# Circuit.net
KiCad netlist of a schematic drawn in EAGLE
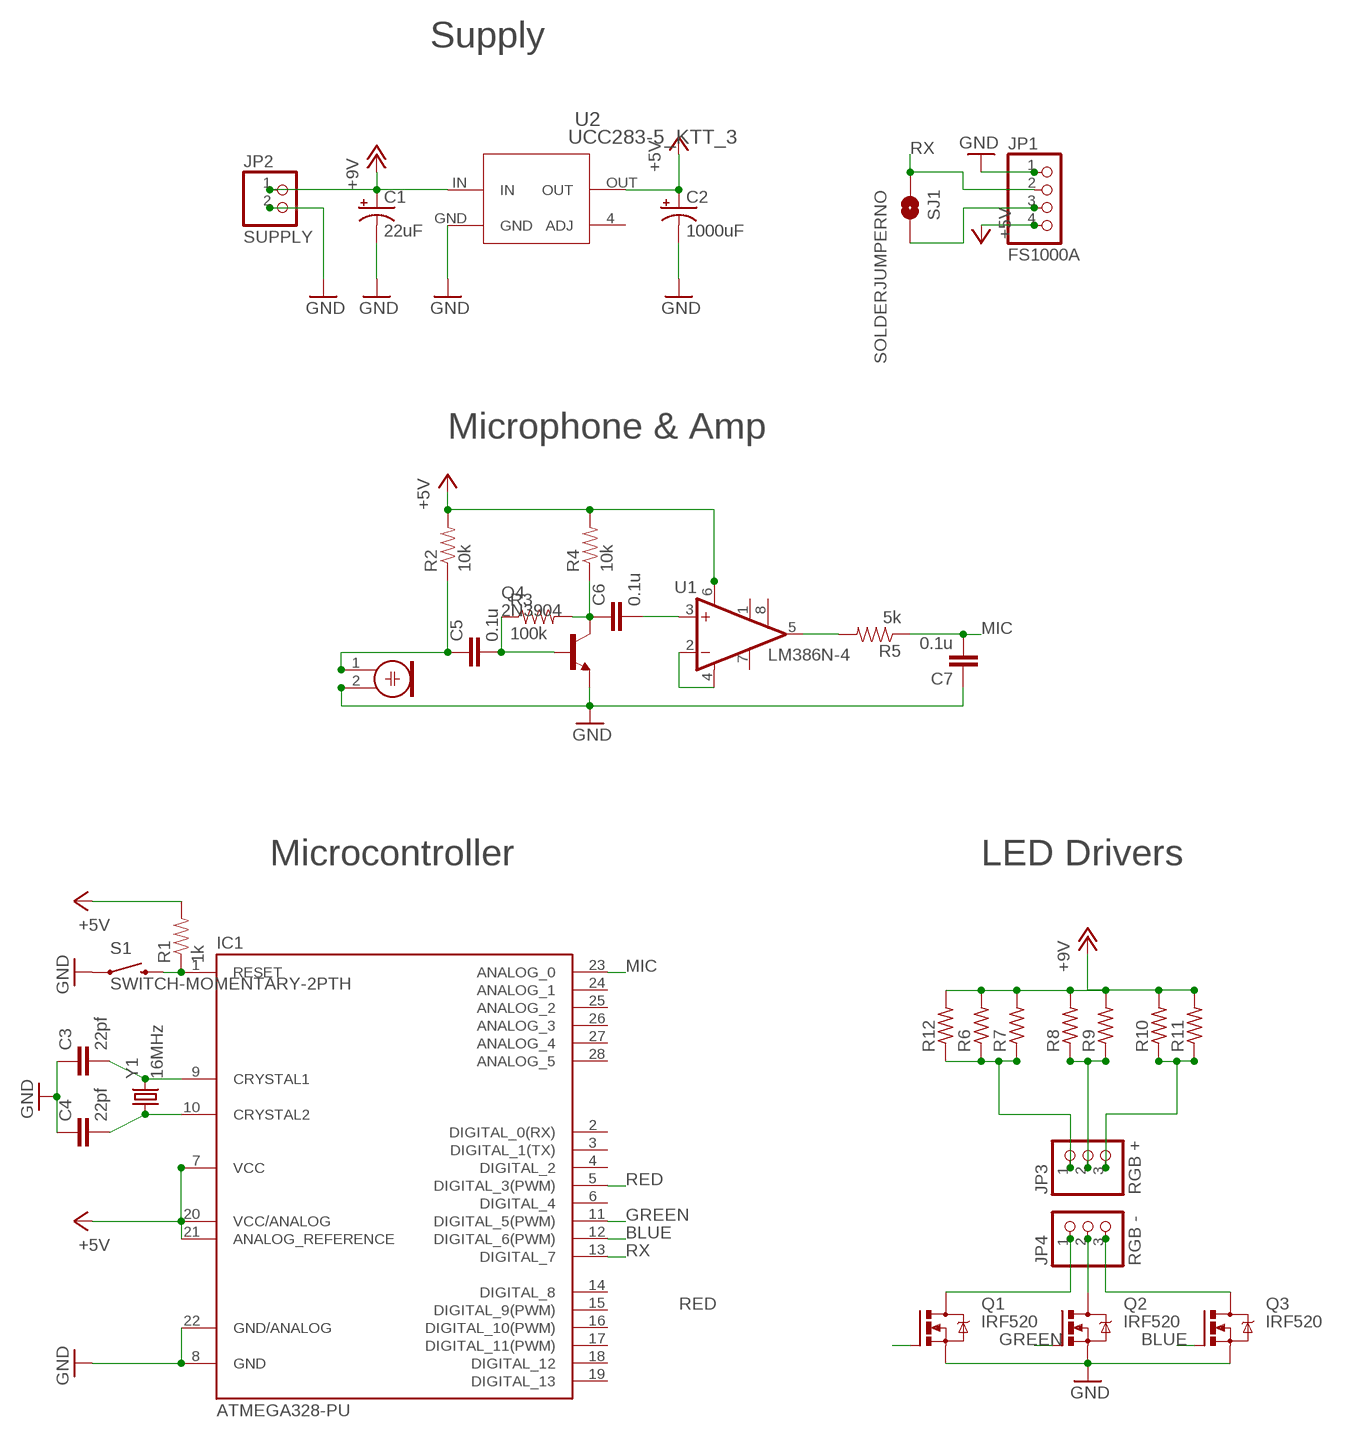
[diagram p0: schematic, sheet 1]

(export (version "E")
  (design (tool "Eeschema 10.0.6"))
  (components
    (comp (ref "C1")
      (value "22uF")
      (footprint "eagle-import:CPOL-RADIAL-10UF-25V")
      (libsource (lib "eagle-import") (part "CAP_POLPTH2"))
    )
    (comp (ref "C2")
      (value "1000uF")
      (footprint "eagle-import:CPOL-RADIAL-1000UF-25V")
      (libsource (lib "eagle-import") (part "CAP_POLPTH4"))
    )
    (comp (ref "C3")
      (value "22pf")
      (footprint "eagle-import:CAP-PTH-SMALL-KIT")
      (libsource (lib "eagle-import") (part "CAPKIT"))
    )
    (comp (ref "C4")
      (value "22pf")
      (footprint "eagle-import:CAP-PTH-SMALL-KIT")
      (libsource (lib "eagle-import") (part "CAPKIT"))
    )
    (comp (ref "C5")
      (value "0.1u")
      (footprint "eagle-import:CAP-PTH-5MM")
      (libsource (lib "eagle-import") (part "CAPPTH1"))
    )
    (comp (ref "C6")
      (value "0.1u")
      (footprint "eagle-import:CAP-PTH-5MM")
      (libsource (lib "eagle-import") (part "CAPPTH1"))
    )
    (comp (ref "C7")
      (value "0.1u")
      (footprint "eagle-import:CAP-PTH-5MM")
      (libsource (lib "eagle-import") (part "CAPPTH1"))
    )
    (comp (ref "IC1")
      (value "ATMEGA328-PU")
      (footprint "eagle-import:DIL28-3")
      (libsource (lib "eagle-import") (part "ATMEGA168-PU"))
    )
    (comp (ref "JP1")
      (value "FS1000A")
      (footprint "eagle-import:1X04")
      (libsource (lib "eagle-import") (part "PINHD-1X4"))
    )
    (comp (ref "JP2")
      (value "SUPPLY")
      (footprint "eagle-import:1X02")
      (libsource (lib "eagle-import") (part "PINHD-1X2"))
    )
    (comp (ref "JP3")
      (value "RGB +")
      (footprint "eagle-import:1X03")
      (libsource (lib "eagle-import") (part "PINHD-1X3"))
    )
    (comp (ref "JP4")
      (value "RGB -")
      (footprint "eagle-import:1X03")
      (libsource (lib "eagle-import") (part "PINHD-1X3"))
    )
    (comp (ref "M1")
      (value "MIC")
      (footprint "eagle-import:WM-62PC_62PK")
      (libsource (lib "eagle-import") (part "ELECTRET_MICROPHON-WM-62PC/62PK"))
    )
    (comp (ref "Q1")
      (value "IRF520")
      (footprint "eagle-import:TO220BV")
      (libsource (lib "eagle-import") (part "IRF520"))
    )
    (comp (ref "Q2")
      (value "IRF520")
      (footprint "eagle-import:TO220BV")
      (libsource (lib "eagle-import") (part "IRF520"))
    )
    (comp (ref "Q3")
      (value "IRF520")
      (footprint "eagle-import:TO220BV")
      (libsource (lib "eagle-import") (part "IRF520"))
    )
    (comp (ref "Q4")
      (value "2N3904")
      (footprint "eagle-import:TO92")
      (libsource (lib "eagle-import") (part "2N3904"))
    )
    (comp (ref "R1")
      (value "1k")
      (footprint "eagle-import:AXIAL-0.3EZ")
      (libsource (lib "eagle-import") (part "RESISTOREZ"))
    )
    (comp (ref "R2")
      (value "10k")
      (footprint "eagle-import:AXIAL-0.3EZ")
      (libsource (lib "eagle-import") (part "RESISTOREZ"))
    )
    (comp (ref "R3")
      (value "100k")
      (footprint "eagle-import:AXIAL-0.3EZ")
      (libsource (lib "eagle-import") (part "RESISTOREZ"))
    )
    (comp (ref "R4")
      (value "10k")
      (footprint "eagle-import:AXIAL-0.3EZ")
      (libsource (lib "eagle-import") (part "RESISTOREZ"))
    )
    (comp (ref "R5")
      (value "5k")
      (footprint "eagle-import:AXIAL-0.3EZ")
      (libsource (lib "eagle-import") (part "RESISTOREZ"))
    )
    (comp (ref "R6")
      (value "R-US_0613/5V")
      (footprint "eagle-import:P0613V")
      (libsource (lib "eagle-import") (part "R-US_0613/5V"))
    )
    (comp (ref "R7")
      (value "R-US_0613/5V")
      (footprint "eagle-import:P0613V")
      (libsource (lib "eagle-import") (part "R-US_0613/5V"))
    )
    (comp (ref "R8")
      (value "R-US_0613/5V")
      (footprint "eagle-import:P0613V")
      (libsource (lib "eagle-import") (part "R-US_0613/5V"))
    )
    (comp (ref "R9")
      (value "R-US_0613/5V")
      (footprint "eagle-import:P0613V")
      (libsource (lib "eagle-import") (part "R-US_0613/5V"))
    )
    (comp (ref "R10")
      (value "R-US_0613/5V")
      (footprint "eagle-import:P0613V")
      (libsource (lib "eagle-import") (part "R-US_0613/5V"))
    )
    (comp (ref "R11")
      (value "R-US_0613/5V")
      (footprint "eagle-import:P0613V")
      (libsource (lib "eagle-import") (part "R-US_0613/5V"))
    )
    (comp (ref "R12")
      (value "R-US_0613/5V")
      (footprint "eagle-import:P0613V")
      (libsource (lib "eagle-import") (part "R-US_0613/5V"))
    )
    (comp (ref "S1")
      (value "SWITCH-MOMENTARY-2PTH")
      (footprint "eagle-import:TACTILE-PTH")
      (libsource (lib "eagle-import") (part "SWITCH-MOMENTARY-2PTH"))
    )
    (comp (ref "SJ1")
      (value "SOLDERJUMPERNO")
      (footprint "eagle-import:SJ_2S-NO")
      (libsource (lib "eagle-import") (part "SOLDERJUMPERNO"))
    )
    (comp (ref "U1")
      (value "LM386N-4")
      (footprint "eagle-import:DIL08")
      (libsource (lib "eagle-import") (part "LM386?-N4"))
    )
    (comp (ref "U2")
      (value "UCC283-5_KTT_3")
      (footprint "eagle-import:KTT3_6P22X6P6")
      (fields
        (field (name "GENERIC_PART_NUMBER") "UCC283-5")
        (field (name "MANUFACTURER") "Texas Instruments")
        (field (name "MANUFACTURER_PART_NUMBER") "ucc283-5_ktt_3")
      )
      (libsource (lib "eagle-import") (part "UCC283-5_KTT_3"))
    )
    (comp (ref "Y1")
      (value "16MHz")
      (footprint "eagle-import:HC49US")
      (libsource (lib "eagle-import") (part "CRYSTALHC49US"))
    )
  )
  (nets
    (net (code "1") (name "+5V") (class "Default")
      (node (ref "C2") (pin "1") (pinfunction "+_1") (pintype "passive"))
      (node (ref "IC1") (pin "20") (pinfunction "VCC/ANALOG_20") (pintype "passive"))
      (node (ref "IC1") (pin "21") (pinfunction "ANALOG_REFERENCE_21") (pintype "passive"))
      (node (ref "IC1") (pin "7") (pinfunction "VCC_7") (pintype "power_in"))
      (node (ref "JP1") (pin "4") (pinfunction "4_4") (pintype "passive"))
      (node (ref "R1") (pin "P$2") (pinfunction "2_P$2") (pintype "passive"))
      (node (ref "R2") (pin "P$2") (pinfunction "2_P$2") (pintype "passive"))
      (node (ref "R4") (pin "P$2") (pinfunction "2_P$2") (pintype "passive"))
      (node (ref "U1") (pin "6") (pinfunction "VS_6") (pintype "power_in"))
      (node (ref "U2") (pin "OUT") (pinfunction "OUT_OUT") (pintype "power_in"))
    )
    (net (code "2") (name "+9V") (class "Default")
      (node (ref "C1") (pin "1") (pinfunction "+_1") (pintype "passive"))
      (node (ref "JP2") (pin "1") (pinfunction "1_1") (pintype "passive"))
      (node (ref "R10") (pin "2") (pinfunction "2_2") (pintype "passive"))
      (node (ref "R11") (pin "2") (pinfunction "2_2") (pintype "passive"))
      (node (ref "R12") (pin "2") (pinfunction "2_2") (pintype "passive"))
      (node (ref "R6") (pin "2") (pinfunction "2_2") (pintype "passive"))
      (node (ref "R7") (pin "2") (pinfunction "2_2") (pintype "passive"))
      (node (ref "R8") (pin "2") (pinfunction "2_2") (pintype "passive"))
      (node (ref "R9") (pin "2") (pinfunction "2_2") (pintype "passive"))
      (node (ref "U2") (pin "IN") (pinfunction "IN_IN") (pintype "power_in"))
    )
    (net (code "3") (name "/BLUE") (class "Default")
      (node (ref "IC1") (pin "12") (pinfunction "DIGITAL_6(PWM)_12") (pintype "bidirectional"))
      (node (ref "Q3") (pin "G") (pinfunction "G_G") (pintype "passive"))
    )
    (net (code "4") (name "/GREEN") (class "Default")
      (node (ref "IC1") (pin "11") (pinfunction "DIGITAL_5(PWM)_11") (pintype "bidirectional"))
      (node (ref "Q2") (pin "G") (pinfunction "G_G") (pintype "passive"))
    )
    (net (code "5") (name "/MIC") (class "Default")
      (node (ref "C7") (pin "2") (pinfunction "2_2") (pintype "passive"))
      (node (ref "IC1") (pin "23") (pinfunction "ANALOG_0_23") (pintype "bidirectional"))
      (node (ref "R5") (pin "P$1") (pinfunction "1_P$1") (pintype "passive"))
    )
    (net (code "6") (name "/RED") (class "Default")
      (node (ref "IC1") (pin "5") (pinfunction "DIGITAL_3(PWM)_5") (pintype "bidirectional"))
      (node (ref "Q1") (pin "G") (pinfunction "G_G") (pintype "passive"))
    )
    (net (code "7") (name "/RX") (class "Default")
      (node (ref "IC1") (pin "13") (pinfunction "DIGITAL_7_13") (pintype "bidirectional"))
      (node (ref "JP1") (pin "2") (pinfunction "2_2") (pintype "passive"))
      (node (ref "SJ1") (pin "1") (pinfunction "1_1") (pintype "passive"))
    )
    (net (code "8") (name "GND") (class "Default")
      (node (ref "C1") (pin "2") (pinfunction "-_2") (pintype "passive"))
      (node (ref "C2") (pin "2") (pinfunction "-_2") (pintype "passive"))
      (node (ref "C3") (pin "1") (pinfunction "1_1") (pintype "passive"))
      (node (ref "C4") (pin "1") (pinfunction "1_1") (pintype "passive"))
      (node (ref "C7") (pin "1") (pinfunction "1_1") (pintype "passive"))
      (node (ref "IC1") (pin "22") (pinfunction "GND/ANALOG_22") (pintype "power_in"))
      (node (ref "IC1") (pin "8") (pinfunction "GND_8") (pintype "power_in"))
      (node (ref "JP1") (pin "1") (pinfunction "1_1") (pintype "passive"))
      (node (ref "JP2") (pin "2") (pinfunction "2_2") (pintype "passive"))
      (node (ref "M1") (pin "2") (pinfunction "2_2") (pintype "passive"))
      (node (ref "Q1") (pin "S") (pinfunction "S_S") (pintype "passive"))
      (node (ref "Q2") (pin "S") (pinfunction "S_S") (pintype "passive"))
      (node (ref "Q3") (pin "S") (pinfunction "S_S") (pintype "passive"))
      (node (ref "Q4") (pin "3") (pinfunction "E_3") (pintype "passive"))
      (node (ref "S1") (pin "1") (pinfunction "1_1") (pintype "passive"))
      (node (ref "U2") (pin "GND") (pinfunction "GND_GND") (pintype "power_in"))
    )
    (net (code "9") (name "Net-(IC1-CRYSTAL1)") (class "Default")
      (node (ref "C3") (pin "2") (pinfunction "2_2") (pintype "passive"))
      (node (ref "IC1") (pin "9") (pinfunction "CRYSTAL1_9") (pintype "bidirectional"))
      (node (ref "Y1") (pin "2") (pinfunction "2_2") (pintype "passive"))
    )
    (net (code "10") (name "Net-(IC1-CRYSTAL2)") (class "Default")
      (node (ref "C4") (pin "2") (pinfunction "2_2") (pintype "passive"))
      (node (ref "IC1") (pin "10") (pinfunction "CRYSTAL2_10") (pintype "bidirectional"))
      (node (ref "Y1") (pin "1") (pinfunction "1_1") (pintype "passive"))
    )
    (net (code "11") (name "Net-(IC1-RESET)") (class "Default")
      (node (ref "IC1") (pin "1") (pinfunction "RESET_1") (pintype "bidirectional"))
      (node (ref "R1") (pin "P$1") (pinfunction "1_P$1") (pintype "passive"))
      (node (ref "S1") (pin "3") (pinfunction "2_3") (pintype "passive"))
    )
    (net (code "12") (name "Net-(JP1-Pad3)") (class "Default")
      (node (ref "JP1") (pin "3") (pinfunction "3_3") (pintype "passive"))
      (node (ref "SJ1") (pin "2") (pinfunction "2_2") (pintype "passive"))
    )
    (net (code "13") (name "Net-(JP3-Pad1)") (class "Default")
      (node (ref "JP3") (pin "1") (pinfunction "1_1") (pintype "passive"))
      (node (ref "R12") (pin "1") (pinfunction "1_1") (pintype "passive"))
      (node (ref "R6") (pin "1") (pinfunction "1_1") (pintype "passive"))
      (node (ref "R7") (pin "1") (pinfunction "1_1") (pintype "passive"))
    )
    (net (code "14") (name "Net-(JP3-Pad2)") (class "Default")
      (node (ref "JP3") (pin "2") (pinfunction "2_2") (pintype "passive"))
      (node (ref "R8") (pin "1") (pinfunction "1_1") (pintype "passive"))
      (node (ref "R9") (pin "1") (pinfunction "1_1") (pintype "passive"))
    )
    (net (code "15") (name "Net-(JP3-Pad3)") (class "Default")
      (node (ref "JP3") (pin "3") (pinfunction "3_3") (pintype "passive"))
      (node (ref "R10") (pin "1") (pinfunction "1_1") (pintype "passive"))
      (node (ref "R11") (pin "1") (pinfunction "1_1") (pintype "passive"))
    )
    (net (code "16") (name "Net-(JP4-Pad1)") (class "Default")
      (node (ref "JP4") (pin "1") (pinfunction "1_1") (pintype "passive"))
      (node (ref "Q1") (pin "D") (pinfunction "D_D") (pintype "passive"))
    )
    (net (code "17") (name "Net-(JP4-Pad2)") (class "Default")
      (node (ref "JP4") (pin "2") (pinfunction "2_2") (pintype "passive"))
      (node (ref "Q2") (pin "D") (pinfunction "D_D") (pintype "passive"))
    )
    (net (code "18") (name "Net-(JP4-Pad3)") (class "Default")
      (node (ref "JP4") (pin "3") (pinfunction "3_3") (pintype "passive"))
      (node (ref "Q3") (pin "D") (pinfunction "D_D") (pintype "passive"))
    )
    (net (code "19") (name "Net-(Q4-B)") (class "Default")
      (node (ref "C5") (pin "2") (pinfunction "2_2") (pintype "passive"))
      (node (ref "Q4") (pin "2") (pinfunction "B_2") (pintype "passive"))
      (node (ref "R3") (pin "P$1") (pinfunction "1_P$1") (pintype "passive"))
    )
    (net (code "20") (name "Net-(Q4-C)") (class "Default")
      (node (ref "C6") (pin "1") (pinfunction "1_1") (pintype "passive"))
      (node (ref "Q4") (pin "1") (pinfunction "C_1") (pintype "passive"))
      (node (ref "R3") (pin "P$2") (pinfunction "2_P$2") (pintype "passive"))
      (node (ref "R4") (pin "P$1") (pinfunction "1_P$1") (pintype "passive"))
    )
    (net (code "21") (name "Net-(R2-1)") (class "Default")
      (node (ref "C5") (pin "1") (pinfunction "1_1") (pintype "passive"))
      (node (ref "M1") (pin "1") (pinfunction "1_1") (pintype "passive"))
      (node (ref "R2") (pin "P$1") (pinfunction "1_P$1") (pintype "passive"))
    )
    (net (code "22") (name "Net-(R5-2)") (class "Default")
      (node (ref "R5") (pin "P$2") (pinfunction "2_P$2") (pintype "passive"))
      (node (ref "U1") (pin "5") (pinfunction "OUT_5") (pintype "output"))
    )
    (net (code "23") (name "Net-(U1-+IN)") (class "Default")
      (node (ref "C6") (pin "2") (pinfunction "2_2") (pintype "passive"))
      (node (ref "U1") (pin "3") (pinfunction "+IN_3") (pintype "input"))
    )
    (net (code "24") (name "Net-(U1--IN)") (class "Default")
      (node (ref "U1") (pin "2") (pinfunction "-IN_2") (pintype "input"))
      (node (ref "U1") (pin "4") (pinfunction "GND_4") (pintype "power_in"))
    )
    (net (code "25") (name "unconnected-(IC1-ANALOG_1-Pad24)") (class "Default")
      (node (ref "IC1") (pin "24") (pinfunction "ANALOG_1_24") (pintype "bidirectional"))
    )
    (net (code "26") (name "unconnected-(IC1-ANALOG_2-Pad25)") (class "Default")
      (node (ref "IC1") (pin "25") (pinfunction "ANALOG_2_25") (pintype "bidirectional"))
    )
    (net (code "27") (name "unconnected-(IC1-ANALOG_3-Pad26)") (class "Default")
      (node (ref "IC1") (pin "26") (pinfunction "ANALOG_3_26") (pintype "bidirectional"))
    )
    (net (code "28") (name "unconnected-(IC1-ANALOG_4-Pad27)") (class "Default")
      (node (ref "IC1") (pin "27") (pinfunction "ANALOG_4_27") (pintype "bidirectional"))
    )
    (net (code "29") (name "unconnected-(IC1-ANALOG_5-Pad28)") (class "Default")
      (node (ref "IC1") (pin "28") (pinfunction "ANALOG_5_28") (pintype "bidirectional"))
    )
    (net (code "30") (name "unconnected-(IC1-DIGITAL_0(RX)-Pad2)") (class "Default")
      (node (ref "IC1") (pin "2") (pinfunction "DIGITAL_0(RX)_2") (pintype "bidirectional"))
    )
    (net (code "31") (name "unconnected-(IC1-DIGITAL_1(TX)-Pad3)") (class "Default")
      (node (ref "IC1") (pin "3") (pinfunction "DIGITAL_1(TX)_3") (pintype "bidirectional"))
    )
    (net (code "32") (name "unconnected-(IC1-DIGITAL_2-Pad4)") (class "Default")
      (node (ref "IC1") (pin "4") (pinfunction "DIGITAL_2_4") (pintype "bidirectional"))
    )
    (net (code "33") (name "unconnected-(IC1-DIGITAL_4-Pad6)") (class "Default")
      (node (ref "IC1") (pin "6") (pinfunction "DIGITAL_4_6") (pintype "bidirectional"))
    )
    (net (code "34") (name "unconnected-(IC1-DIGITAL_8-Pad14)") (class "Default")
      (node (ref "IC1") (pin "14") (pinfunction "DIGITAL_8_14") (pintype "bidirectional"))
    )
    (net (code "35") (name "unconnected-(IC1-DIGITAL_9(PWM)-Pad15)") (class "Default")
      (node (ref "IC1") (pin "15") (pinfunction "DIGITAL_9(PWM)_15") (pintype "bidirectional"))
    )
    (net (code "36") (name "unconnected-(IC1-DIGITAL_10(PWM)-Pad16)") (class "Default")
      (node (ref "IC1") (pin "16") (pinfunction "DIGITAL_10(PWM)_16") (pintype "bidirectional"))
    )
    (net (code "37") (name "unconnected-(IC1-DIGITAL_11(PWM)-Pad17)") (class "Default")
      (node (ref "IC1") (pin "17") (pinfunction "DIGITAL_11(PWM)_17") (pintype "bidirectional"))
    )
    (net (code "38") (name "unconnected-(IC1-DIGITAL_12-Pad18)") (class "Default")
      (node (ref "IC1") (pin "18") (pinfunction "DIGITAL_12_18") (pintype "bidirectional"))
    )
    (net (code "39") (name "unconnected-(IC1-DIGITAL_13-Pad19)") (class "Default")
      (node (ref "IC1") (pin "19") (pinfunction "DIGITAL_13_19") (pintype "bidirectional"))
    )
    (net (code "40") (name "unconnected-(U1-BYPASS-Pad7)") (class "Default")
      (node (ref "U1") (pin "7") (pinfunction "BYPASS_7") (pintype "passive"))
    )
    (net (code "41") (name "unconnected-(U1-GAIN-Pad1)") (class "Default")
      (node (ref "U1") (pin "1") (pinfunction "GAIN_1") (pintype "passive"))
    )
    (net (code "42") (name "unconnected-(U1-GAIN-Pad8)") (class "Default")
      (node (ref "U1") (pin "8") (pinfunction "GAIN_8") (pintype "passive"))
    )
    (net (code "43") (name "unconnected-(U2-ADJ-Pad4)") (class "Default")
      (node (ref "U2") (pin "4") (pinfunction "ADJ_4") (pintype "passive"))
    )
  )
)
